# Senior_Design_PCB.net
KiCad netlist of a schematic drawn in EAGLE
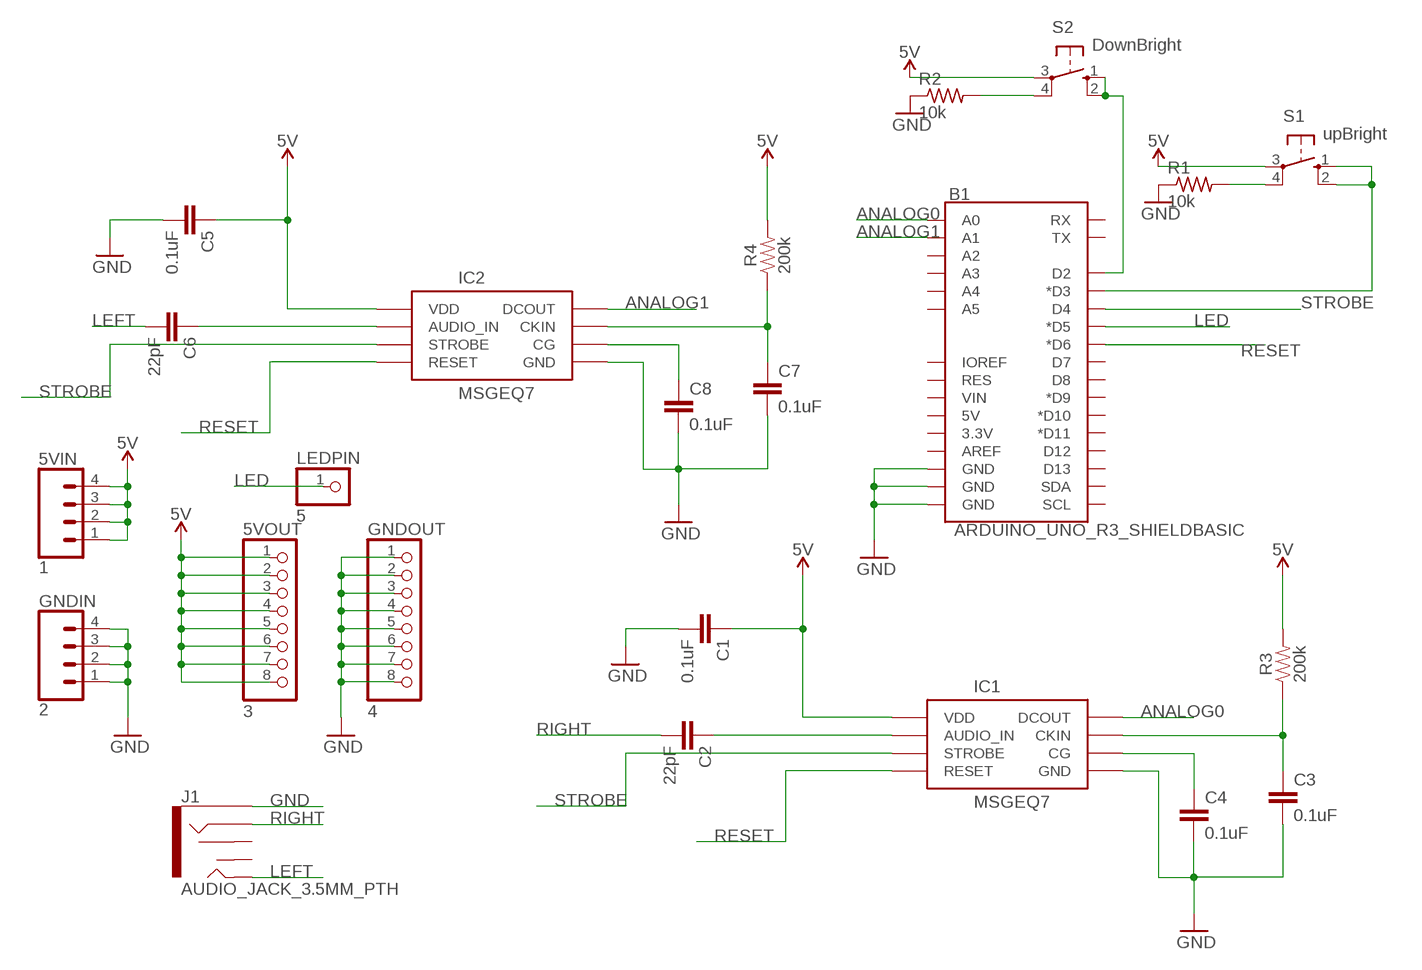
[diagram p0: schematic, sheet 1]

(export (version "E")
  (design (tool "Eeschema 10.0.6"))
  (components
    (comp (ref "5VIN")
      (value "1")
      (footprint "eagle-import:1X04")
      (libsource (lib "eagle-import") (part "CONN_04"))
    )
    (comp (ref "5VOUT")
      (value "3")
      (footprint "eagle-import:1X08-BIG")
      (libsource (lib "eagle-import") (part "PINHD-1X8BIG"))
    )
    (comp (ref "B1")
      (value "ARDUINO_UNO_R3_SHIELDBASIC")
      (footprint "eagle-import:UNO_R3_SHIELD")
      (libsource (lib "eagle-import") (part "ARDUINO_UNO_R3_SHIELDBASIC"))
    )
    (comp (ref "C1")
      (value "0.1uF")
      (footprint "eagle-import:CAP-PTH-SMALL-KIT")
      (libsource (lib "eagle-import") (part "0.1UF-KIT-EZ-50V-20%"))
    )
    (comp (ref "C2")
      (value "22pF")
      (footprint "eagle-import:CAP-PTH-2.54")
      (libsource (lib "eagle-import") (part "22PF-PTH-2.54MM-200V-5%"))
    )
    (comp (ref "C3")
      (value "0.1uF")
      (footprint "eagle-import:CAP-PTH-SMALL-KIT")
      (libsource (lib "eagle-import") (part "0.1UF-KIT-EZ-50V-20%"))
    )
    (comp (ref "C4")
      (value "0.1uF")
      (footprint "eagle-import:CAP-PTH-SMALL-KIT")
      (libsource (lib "eagle-import") (part "0.1UF-KIT-EZ-50V-20%"))
    )
    (comp (ref "C5")
      (value "0.1uF")
      (footprint "eagle-import:CAP-PTH-SMALL-KIT")
      (libsource (lib "eagle-import") (part "0.1UF-KIT-EZ-50V-20%"))
    )
    (comp (ref "C6")
      (value "22pF")
      (footprint "eagle-import:CAP-PTH-2.54")
      (libsource (lib "eagle-import") (part "22PF-PTH-2.54MM-200V-5%"))
    )
    (comp (ref "C7")
      (value "0.1uF")
      (footprint "eagle-import:CAP-PTH-SMALL-KIT")
      (fields (field (name "SPICEPREFIX") "C"))
      (libsource (lib "eagle-import") (part "0.1UF-KIT-EZ-50V-20%"))
    )
    (comp (ref "C8")
      (value "0.1uF")
      (footprint "eagle-import:CAP-PTH-SMALL-KIT")
      (libsource (lib "eagle-import") (part "0.1UF-KIT-EZ-50V-20%"))
    )
    (comp (ref "GNDIN")
      (value "2")
      (footprint "eagle-import:1X04")
      (libsource (lib "eagle-import") (part "CONN_04"))
    )
    (comp (ref "GNDOUT")
      (value "4")
      (footprint "eagle-import:1X08-BIG")
      (libsource (lib "eagle-import") (part "PINHD-1X8BIG"))
    )
    (comp (ref "IC1")
      (value "MSGEQ7P")
      (footprint "eagle-import:DIP08")
      (libsource (lib "eagle-import") (part "MSGEQ7DIL"))
    )
    (comp (ref "IC2")
      (value "MSGEQ7P")
      (footprint "eagle-import:DIP08")
      (libsource (lib "eagle-import") (part "MSGEQ7DIL"))
    )
    (comp (ref "J1")
      (value "AUDIO_JACK_3.5MM_PTH")
      (footprint "eagle-import:AUDIO-JACK")
      (libsource (lib "eagle-import") (part "AUDIO_JACK_3.5MM_PTH"))
    )
    (comp (ref "LEDPIN")
      (value "5")
      (footprint "eagle-import:1X01")
      (libsource (lib "eagle-import") (part "PINHD-1X1"))
    )
    (comp (ref "R1")
      (value "10k")
      (footprint "eagle-import:0204_7")
      (libsource (lib "eagle-import") (part "R-US_0204/7"))
    )
    (comp (ref "R2")
      (value "10k")
      (footprint "eagle-import:0204_7")
      (libsource (lib "eagle-import") (part "R-US_0204/7"))
    )
    (comp (ref "R3")
      (value "200k")
      (footprint "eagle-import:AXIAL-0.3")
      (libsource (lib "eagle-import") (part "100KOHM-HORIZ-1/4W-5%"))
    )
    (comp (ref "R4")
      (value "200k")
      (footprint "eagle-import:AXIAL-0.3")
      (libsource (lib "eagle-import") (part "100KOHM-HORIZ-1/4W-5%"))
    )
    (comp (ref "S1")
      (value "upBright")
      (footprint "eagle-import:B3F-40XX")
      (fields (field (name "MF") "OMRON COMPONENTS USA") (field (name "MPN") "B3F-4000"))
      (libsource (lib "eagle-import") (part "40-XX"))
    )
    (comp (ref "S2")
      (value "DownBright")
      (footprint "eagle-import:B3F-40XX")
      (fields (field (name "MF") "OMRON COMPONENTS USA") (field (name "MPN") "B3F-4000"))
      (libsource (lib "eagle-import") (part "40-XX"))
    )
  )
  (nets
    (net (code "1") (name "/ANALOG0") (class "Default")
      (node (ref "B1") (pin "A0") (pinfunction "A0_A0") (pintype "bidirectional"))
      (node (ref "IC1") (pin "3") (pinfunction "DCOUT_3") (pintype "bidirectional"))
    )
    (net (code "2") (name "/ANALOG1") (class "Default")
      (node (ref "B1") (pin "A1") (pinfunction "A1_A1") (pintype "bidirectional"))
      (node (ref "IC2") (pin "3") (pinfunction "DCOUT_3") (pintype "bidirectional"))
    )
    (net (code "3") (name "/LED") (class "Default")
      (node (ref "B1") (pin "D5") (pinfunction "*D5_D5") (pintype "bidirectional"))
      (node (ref "LEDPIN") (pin "1") (pinfunction "1_1") (pintype "passive"))
    )
    (net (code "4") (name "/LEFT") (class "Default")
      (node (ref "C6") (pin "2") (pinfunction "2_2") (pintype "passive"))
      (node (ref "J1") (pin "TIP") (pinfunction "TIP_TIP") (pintype "bidirectional"))
    )
    (net (code "5") (name "/RESET") (class "Default")
      (node (ref "B1") (pin "D6") (pinfunction "*D6_D6") (pintype "bidirectional"))
      (node (ref "IC1") (pin "7") (pinfunction "RESET_7") (pintype "input"))
      (node (ref "IC2") (pin "7") (pinfunction "RESET_7") (pintype "input"))
    )
    (net (code "6") (name "/RIGHT") (class "Default")
      (node (ref "C2") (pin "2") (pinfunction "2_2") (pintype "passive"))
      (node (ref "J1") (pin "RING") (pinfunction "RING_RING") (pintype "bidirectional"))
    )
    (net (code "7") (name "/STROBE") (class "Default")
      (node (ref "B1") (pin "D4") (pinfunction "D4_D4") (pintype "bidirectional"))
      (node (ref "IC1") (pin "4") (pinfunction "STROBE_4") (pintype "input"))
      (node (ref "IC2") (pin "4") (pinfunction "STROBE_4") (pintype "input"))
    )
    (net (code "8") (name "5V") (class "Default")
      (node (ref "5VIN") (pin "1") (pinfunction "1_1") (pintype "passive"))
      (node (ref "5VIN") (pin "2") (pinfunction "2_2") (pintype "passive"))
      (node (ref "5VIN") (pin "3") (pinfunction "3_3") (pintype "passive"))
      (node (ref "5VIN") (pin "4") (pinfunction "4_4") (pintype "passive"))
      (node (ref "5VOUT") (pin "1") (pinfunction "1_1") (pintype "passive"))
      (node (ref "5VOUT") (pin "2") (pinfunction "2_2") (pintype "passive"))
      (node (ref "5VOUT") (pin "3") (pinfunction "3_3") (pintype "passive"))
      (node (ref "5VOUT") (pin "4") (pinfunction "4_4") (pintype "passive"))
      (node (ref "5VOUT") (pin "5") (pinfunction "5_5") (pintype "passive"))
      (node (ref "5VOUT") (pin "6") (pinfunction "6_6") (pintype "passive"))
      (node (ref "5VOUT") (pin "7") (pinfunction "7_7") (pintype "passive"))
      (node (ref "5VOUT") (pin "8") (pinfunction "8_8") (pintype "passive"))
      (node (ref "C1") (pin "1") (pinfunction "1_1") (pintype "passive"))
      (node (ref "C5") (pin "1") (pinfunction "1_1") (pintype "passive"))
      (node (ref "IC1") (pin "1") (pinfunction "VDD_1") (pintype "input"))
      (node (ref "IC2") (pin "1") (pinfunction "VDD_1") (pintype "input"))
      (node (ref "R3") (pin "P$2") (pinfunction "2_P$2") (pintype "passive"))
      (node (ref "R4") (pin "P$2") (pinfunction "2_P$2") (pintype "passive"))
      (node (ref "S1") (pin "3") (pinfunction "P_3") (pintype "passive"))
      (node (ref "S2") (pin "3") (pinfunction "P_3") (pintype "passive"))
    )
    (net (code "9") (name "GND") (class "Default")
      (node (ref "B1") (pin "GND@0") (pinfunction "GND_GND@0") (pintype "bidirectional"))
      (node (ref "B1") (pin "GND@1") (pinfunction "GND_GND@1") (pintype "bidirectional"))
      (node (ref "B1") (pin "GND@2") (pinfunction "GND_GND@2") (pintype "bidirectional"))
      (node (ref "C1") (pin "2") (pinfunction "2_2") (pintype "passive"))
      (node (ref "C3") (pin "2") (pinfunction "2_2") (pintype "passive"))
      (node (ref "C4") (pin "2") (pinfunction "2_2") (pintype "passive"))
      (node (ref "C5") (pin "2") (pinfunction "2_2") (pintype "passive"))
      (node (ref "C7") (pin "2") (pinfunction "2_2") (pintype "passive"))
      (node (ref "C8") (pin "2") (pinfunction "2_2") (pintype "passive"))
      (node (ref "GNDIN") (pin "1") (pinfunction "1_1") (pintype "passive"))
      (node (ref "GNDIN") (pin "2") (pinfunction "2_2") (pintype "passive"))
      (node (ref "GNDIN") (pin "3") (pinfunction "3_3") (pintype "passive"))
      (node (ref "GNDIN") (pin "4") (pinfunction "4_4") (pintype "passive"))
      (node (ref "GNDOUT") (pin "1") (pinfunction "1_1") (pintype "passive"))
      (node (ref "GNDOUT") (pin "2") (pinfunction "2_2") (pintype "passive"))
      (node (ref "GNDOUT") (pin "3") (pinfunction "3_3") (pintype "passive"))
      (node (ref "GNDOUT") (pin "4") (pinfunction "4_4") (pintype "passive"))
      (node (ref "GNDOUT") (pin "5") (pinfunction "5_5") (pintype "passive"))
      (node (ref "GNDOUT") (pin "6") (pinfunction "6_6") (pintype "passive"))
      (node (ref "GNDOUT") (pin "7") (pinfunction "7_7") (pintype "passive"))
      (node (ref "GNDOUT") (pin "8") (pinfunction "8_8") (pintype "passive"))
      (node (ref "IC1") (pin "2") (pinfunction "GND_2") (pintype "bidirectional"))
      (node (ref "IC2") (pin "2") (pinfunction "GND_2") (pintype "bidirectional"))
      (node (ref "J1") (pin "SLEEVE") (pinfunction "SLEEVE_SLEEVE") (pintype "bidirectional"))
      (node (ref "R1") (pin "1") (pinfunction "1_1") (pintype "passive"))
      (node (ref "R2") (pin "1") (pinfunction "1_1") (pintype "passive"))
    )
    (net (code "10") (name "Net-(B1-*D3)") (class "Default")
      (node (ref "B1") (pin "D3") (pinfunction "*D3_D3") (pintype "bidirectional"))
      (node (ref "S1") (pin "1") (pinfunction "S_1") (pintype "passive"))
      (node (ref "S1") (pin "2") (pinfunction "S1_2") (pintype "passive"))
    )
    (net (code "11") (name "Net-(IC1-AUDIO_IN)") (class "Default")
      (node (ref "C2") (pin "1") (pinfunction "1_1") (pintype "passive"))
      (node (ref "IC1") (pin "5") (pinfunction "AUDIO_IN_5") (pintype "input"))
    )
    (net (code "12") (name "Net-(IC1-CG)") (class "Default")
      (node (ref "C4") (pin "1") (pinfunction "1_1") (pintype "passive"))
      (node (ref "IC1") (pin "6") (pinfunction "CG_6") (pintype "bidirectional"))
    )
    (net (code "13") (name "Net-(IC1-CKIN)") (class "Default")
      (node (ref "C3") (pin "1") (pinfunction "1_1") (pintype "passive"))
      (node (ref "IC1") (pin "8") (pinfunction "CKIN_8") (pintype "bidirectional"))
      (node (ref "R3") (pin "P$1") (pinfunction "1_P$1") (pintype "passive"))
    )
    (net (code "14") (name "Net-(IC2-AUDIO_IN)") (class "Default")
      (node (ref "C6") (pin "1") (pinfunction "1_1") (pintype "passive"))
      (node (ref "IC2") (pin "5") (pinfunction "AUDIO_IN_5") (pintype "input"))
    )
    (net (code "15") (name "Net-(IC2-CG)") (class "Default")
      (node (ref "C8") (pin "1") (pinfunction "1_1") (pintype "passive"))
      (node (ref "IC2") (pin "6") (pinfunction "CG_6") (pintype "bidirectional"))
    )
    (net (code "16") (name "Net-(IC2-CKIN)") (class "Default")
      (node (ref "C7") (pin "1") (pinfunction "1_1") (pintype "passive"))
      (node (ref "IC2") (pin "8") (pinfunction "CKIN_8") (pintype "bidirectional"))
      (node (ref "R4") (pin "P$1") (pinfunction "1_P$1") (pintype "passive"))
    )
    (net (code "17") (name "Net-(S1-P1)") (class "Default")
      (node (ref "R1") (pin "2") (pinfunction "2_2") (pintype "passive"))
      (node (ref "S1") (pin "4") (pinfunction "P1_4") (pintype "passive"))
    )
    (net (code "18") (name "Net-(S2-P1)") (class "Default")
      (node (ref "R2") (pin "2") (pinfunction "2_2") (pintype "passive"))
      (node (ref "S2") (pin "4") (pinfunction "P1_4") (pintype "passive"))
    )
    (net (code "19") (name "Net-(S2-S)") (class "Default")
      (node (ref "B1") (pin "D2") (pinfunction "D2_D2") (pintype "bidirectional"))
      (node (ref "S2") (pin "1") (pinfunction "S_1") (pintype "passive"))
      (node (ref "S2") (pin "2") (pinfunction "S1_2") (pintype "passive"))
    )
    (net (code "20") (name "unconnected-(B1-*D9-PadD9)") (class "Default")
      (node (ref "B1") (pin "D9") (pinfunction "*D9_D9") (pintype "bidirectional"))
    )
    (net (code "21") (name "unconnected-(B1-*D10-PadD10)") (class "Default")
      (node (ref "B1") (pin "D10") (pinfunction "*D10_D10") (pintype "bidirectional"))
    )
    (net (code "22") (name "unconnected-(B1-*D11-PadD11)") (class "Default")
      (node (ref "B1") (pin "D11") (pinfunction "*D11_D11") (pintype "bidirectional"))
    )
    (net (code "23") (name "unconnected-(B1-Pad3.3V)") (class "Default")
      (node (ref "B1") (pin "3.3V") (pinfunction "3.3V_3.3V") (pintype "bidirectional"))
    )
    (net (code "24") (name "unconnected-(B1-Pad5V)") (class "Default")
      (node (ref "B1") (pin "5V") (pinfunction "5V_5V") (pintype "bidirectional"))
    )
    (net (code "25") (name "unconnected-(B1-PadA2)") (class "Default")
      (node (ref "B1") (pin "A2") (pinfunction "A2_A2") (pintype "bidirectional"))
    )
    (net (code "26") (name "unconnected-(B1-PadA3)") (class "Default")
      (node (ref "B1") (pin "A3") (pinfunction "A3_A3") (pintype "bidirectional"))
    )
    (net (code "27") (name "unconnected-(B1-PadA4)") (class "Default")
      (node (ref "B1") (pin "A4") (pinfunction "A4_A4") (pintype "bidirectional"))
    )
    (net (code "28") (name "unconnected-(B1-PadA5)") (class "Default")
      (node (ref "B1") (pin "A5") (pinfunction "A5_A5") (pintype "bidirectional"))
    )
    (net (code "29") (name "unconnected-(B1-PadAREF)") (class "Default")
      (node (ref "B1") (pin "AREF") (pinfunction "AREF_AREF") (pintype "bidirectional"))
    )
    (net (code "30") (name "unconnected-(B1-PadD7)") (class "Default")
      (node (ref "B1") (pin "D7") (pinfunction "D7_D7") (pintype "bidirectional"))
    )
    (net (code "31") (name "unconnected-(B1-PadD8)") (class "Default")
      (node (ref "B1") (pin "D8") (pinfunction "D8_D8") (pintype "bidirectional"))
    )
    (net (code "32") (name "unconnected-(B1-PadD12)") (class "Default")
      (node (ref "B1") (pin "D12") (pinfunction "D12_D12") (pintype "bidirectional"))
    )
    (net (code "33") (name "unconnected-(B1-PadD13)") (class "Default")
      (node (ref "B1") (pin "D13") (pinfunction "D13_D13") (pintype "bidirectional"))
    )
    (net (code "34") (name "unconnected-(B1-PadIOREF)") (class "Default")
      (node (ref "B1") (pin "IOREF") (pinfunction "IOREF_IOREF") (pintype "bidirectional"))
    )
    (net (code "35") (name "unconnected-(B1-PadRES)") (class "Default")
      (node (ref "B1") (pin "RES") (pinfunction "RES_RES") (pintype "bidirectional"))
    )
    (net (code "36") (name "unconnected-(B1-PadRX)") (class "Default")
      (node (ref "B1") (pin "RX") (pinfunction "RX_RX") (pintype "bidirectional"))
    )
    (net (code "37") (name "unconnected-(B1-PadSCL)") (class "Default")
      (node (ref "B1") (pin "SCL") (pinfunction "SCL_SCL") (pintype "bidirectional"))
    )
    (net (code "38") (name "unconnected-(B1-PadSDA)") (class "Default")
      (node (ref "B1") (pin "SDA") (pinfunction "SDA_SDA") (pintype "bidirectional"))
    )
    (net (code "39") (name "unconnected-(B1-PadTX)") (class "Default")
      (node (ref "B1") (pin "TX") (pinfunction "TX_TX") (pintype "bidirectional"))
    )
    (net (code "40") (name "unconnected-(B1-PadVIN)") (class "Default")
      (node (ref "B1") (pin "VIN") (pinfunction "VIN_VIN") (pintype "bidirectional"))
    )
    (net (code "41") (name "unconnected-(J1-PadRSH)") (class "Default")
      (node (ref "J1") (pin "RSH") (pinfunction "RSH_RSH") (pintype "bidirectional"))
    )
    (net (code "42") (name "unconnected-(J1-PadTSH)") (class "Default")
      (node (ref "J1") (pin "TSH") (pinfunction "TSH_TSH") (pintype "bidirectional"))
    )
  )
)
